# 02-USER_IO.net
KiCad netlist of a schematic drawn in Altium Designer
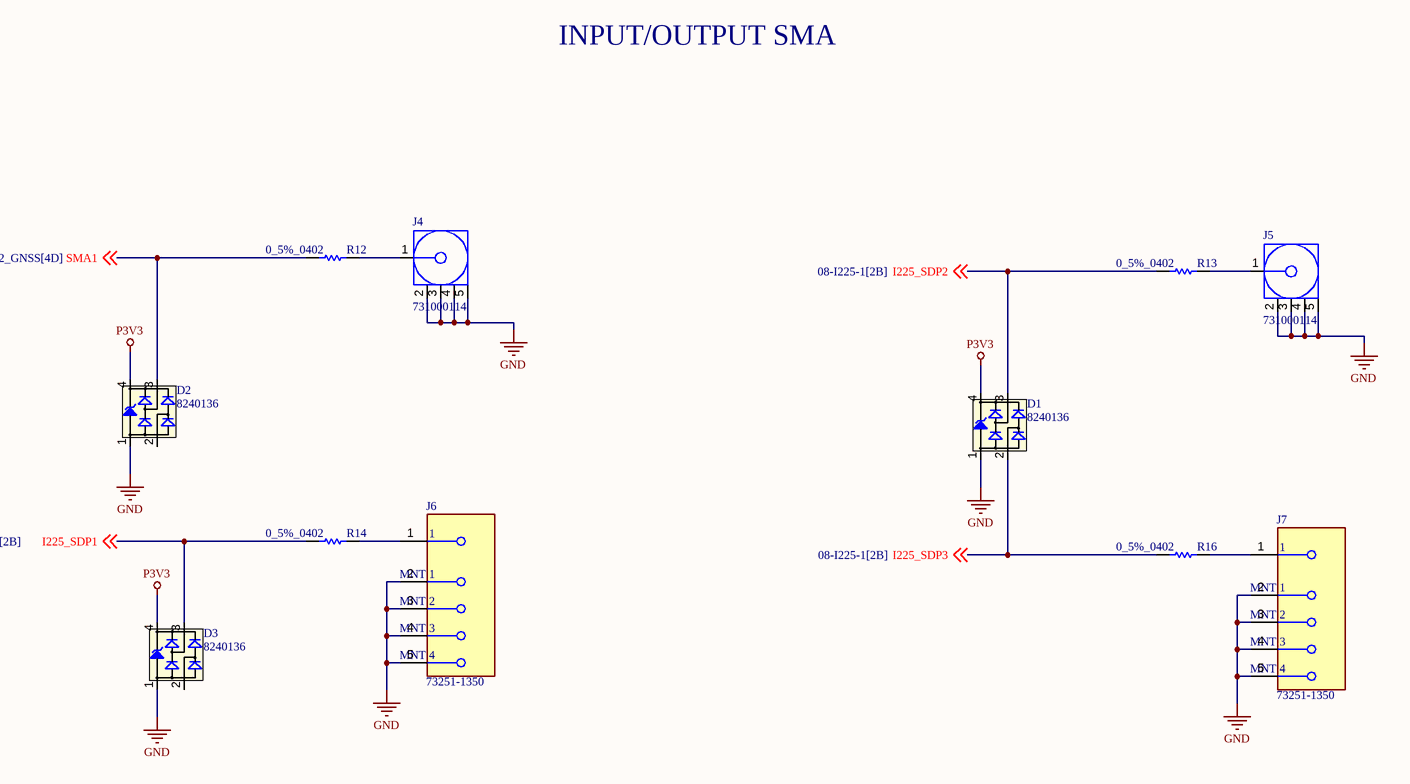
[diagram p0: 02-USER_IO.SchDoc]

(export (version "E")
  (design (tool "Eeschema 10.0.6"))
  (components
    (comp (ref "D1")
      (value "8240136")
      (footprint "SOT143-4L")
      (description "TVS Diode WE-TVS-HS, VRWM=3.3V")
      (fields (field (name "MANUFACTURER") "Wuerth Elektronik"))
      (libsource (lib "Altium Content Vault") (part "WE-TVS-HS-4"))
    )
    (comp (ref "D2")
      (value "8240136")
      (footprint "SOT143-4L")
      (description "TVS Diode WE-TVS-HS, VRWM=3.3V")
      (fields (field (name "MANUFACTURER") "Wuerth Elektronik"))
      (libsource (lib "Altium Content Vault") (part "WE-TVS-HS-4"))
    )
    (comp (ref "D3")
      (value "8240136")
      (footprint "SOT143-4L")
      (description "TVS Diode WE-TVS-HS, VRWM=3.3V")
      (fields (field (name "MANUFACTURER") "Wuerth Elektronik"))
      (libsource (lib "Altium Content Vault") (part "WE-TVS-HS-4"))
    )
    (comp (ref "J4")
      (value "731000114")
      (footprint "MOLX-731000114_V")
      (description "SMA Right-Angle PCB Jack Receptacle, Brass Body, Gold Plated, 50 Ohm, 5-Pin THD, RoHS, Tray")
      (fields (field (name "MANUFACTURER") "Molex"))
      (libsource (lib "Altium Content Vault") (part "CN-S-4F-RF5"))
    )
    (comp (ref "J5")
      (value "731000114")
      (footprint "MOLX-731000114_V")
      (description "SMA Right-Angle PCB Jack Receptacle, Brass Body, Gold Plated, 50 Ohm, 5-Pin THD, RoHS, Tray")
      (fields (field (name "MANUFACTURER") "Molex"))
      (libsource (lib "Altium Content Vault") (part "CN-S-4F-RF5"))
    )
    (comp (ref "J6")
      (value "73251-1350")
      (footprint "FP-73251-1350-MFG")
      (description "CONN SMA JACK STR 50 OHM SMD")
      (fields
        (field (name "OCTOPART") "https://octopart.com/73251-1350-molex-5414390")
        (field (name "MANUFACTURER") "Molex")
      )
      (libsource (lib "Altium Content Vault") (part "474d33b8a96b1ade9ed6dd87a2b06d4"))
    )
    (comp (ref "J7")
      (value "73251-1350")
      (footprint "FP-73251-1350-MFG")
      (description "CONN SMA JACK STR 50 OHM SMD")
      (fields
        (field (name "OCTOPART") "https://octopart.com/73251-1350-molex-5414390")
        (field (name "MANUFACTURER") "Molex")
      )
      (libsource (lib "Altium Content Vault") (part "474d33b8a96b1ade9ed6dd87a2b06d4"))
    )
    (comp (ref "R12")
      (value "0_5%_0402")
      (footprint "RESC1005X40X25LL10T10")
      (fields (field (name "MANUFACTURER") "KOA Speer") (field (name "PART NUMBER") "RK73Z1ETTP"))
      (libsource (lib "Altium Content Vault") (part "RES"))
    )
    (comp (ref "R13")
      (value "0_5%_0402")
      (footprint "RESC1005X40X25LL10T10")
      (fields (field (name "MANUFACTURER") "KOA Speer") (field (name "PART NUMBER") "RK73Z1ETTP"))
      (libsource (lib "Altium Content Vault") (part "RES"))
    )
    (comp (ref "R14")
      (value "0_5%_0402")
      (footprint "RESC1005X40X25LL10T10")
      (fields (field (name "MANUFACTURER") "KOA Speer") (field (name "PART NUMBER") "RK73Z1ETTP"))
      (libsource (lib "Altium Content Vault") (part "RES"))
    )
    (comp (ref "R16")
      (value "0_5%_0402")
      (footprint "RESC1005X40X25LL10T10")
      (fields (field (name "MANUFACTURER") "KOA Speer") (field (name "PART NUMBER") "RK73Z1ETTP"))
      (libsource (lib "Altium Content Vault") (part "RES"))
    )
  )
  (nets
    (net (code "1") (name "GND") (class "Default")
      (node (ref "D1") (pin "1") (pinfunction "GND_1") (pintype "passive"))
      (node (ref "D2") (pin "1") (pinfunction "GND_1") (pintype "passive"))
      (node (ref "D3") (pin "1") (pinfunction "GND_1") (pintype "passive"))
      (node (ref "J4") (pin "2") (pinfunction "2_2") (pintype "passive"))
      (node (ref "J4") (pin "3") (pinfunction "3_3") (pintype "passive"))
      (node (ref "J4") (pin "4") (pinfunction "4_4") (pintype "passive"))
      (node (ref "J4") (pin "5") (pinfunction "5_5") (pintype "passive"))
      (node (ref "J5") (pin "2") (pinfunction "2_2") (pintype "passive"))
      (node (ref "J5") (pin "3") (pinfunction "3_3") (pintype "passive"))
      (node (ref "J5") (pin "4") (pinfunction "4_4") (pintype "passive"))
      (node (ref "J5") (pin "5") (pinfunction "5_5") (pintype "passive"))
      (node (ref "J6") (pin "2") (pinfunction "MNT_1_2") (pintype "passive"))
      (node (ref "J6") (pin "3") (pinfunction "MNT_2_3") (pintype "passive"))
      (node (ref "J6") (pin "4") (pinfunction "MNT_3_4") (pintype "passive"))
      (node (ref "J6") (pin "5") (pinfunction "MNT_4_5") (pintype "passive"))
      (node (ref "J7") (pin "2") (pinfunction "MNT_1_2") (pintype "passive"))
      (node (ref "J7") (pin "3") (pinfunction "MNT_2_3") (pintype "passive"))
      (node (ref "J7") (pin "4") (pinfunction "MNT_3_4") (pintype "passive"))
      (node (ref "J7") (pin "5") (pinfunction "MNT_4_5") (pintype "passive"))
    )
    (net (code "2") (name "I225_SDP1") (class "Default")
      (node (ref "D3") (pin "3") (pinfunction "I/O2_3") (pintype "passive"))
      (node (ref "R14") (pin "1") (pinfunction "1_1") (pintype "passive"))
    )
    (net (code "3") (name "I225_SDP2") (class "Default")
      (node (ref "D1") (pin "3") (pinfunction "I/O2_3") (pintype "passive"))
      (node (ref "R13") (pin "1") (pinfunction "1_1") (pintype "passive"))
    )
    (net (code "4") (name "I225_SDP3") (class "Default")
      (node (ref "D1") (pin "2") (pinfunction "I/O1_2") (pintype "passive"))
      (node (ref "R16") (pin "1") (pinfunction "1_1") (pintype "passive"))
    )
    (net (code "5") (name "Net-(J4-Pad1)") (class "Default")
      (node (ref "J4") (pin "1") (pinfunction "1_1") (pintype "passive"))
      (node (ref "R12") (pin "2") (pinfunction "2_2") (pintype "passive"))
    )
    (net (code "6") (name "Net-(J5-Pad1)") (class "Default")
      (node (ref "J5") (pin "1") (pinfunction "1_1") (pintype "passive"))
      (node (ref "R13") (pin "2") (pinfunction "2_2") (pintype "passive"))
    )
    (net (code "7") (name "Net-(J6-Pad1)") (class "Default")
      (node (ref "J6") (pin "1") (pinfunction "1_1") (pintype "passive"))
      (node (ref "R14") (pin "2") (pinfunction "2_2") (pintype "passive"))
    )
    (net (code "8") (name "Net-(J7-Pad1)") (class "Default")
      (node (ref "J7") (pin "1") (pinfunction "1_1") (pintype "passive"))
      (node (ref "R16") (pin "2") (pinfunction "2_2") (pintype "passive"))
    )
    (net (code "9") (name "P3V3") (class "Default")
      (node (ref "D1") (pin "4") (pinfunction "VDD_4") (pintype "passive"))
      (node (ref "D2") (pin "4") (pinfunction "VDD_4") (pintype "passive"))
      (node (ref "D3") (pin "4") (pinfunction "VDD_4") (pintype "passive"))
    )
    (net (code "10") (name "SMA1") (class "Default")
      (node (ref "D2") (pin "3") (pinfunction "I/O2_3") (pintype "passive"))
      (node (ref "R12") (pin "1") (pinfunction "1_1") (pintype "passive"))
    )
    (net (code "11") (name "unconnected-(D2-I{slash}O1-Pad2)") (class "Default")
      (node (ref "D2") (pin "2") (pinfunction "I/O1_2") (pintype "passive"))
    )
    (net (code "12") (name "unconnected-(D3-I{slash}O1-Pad2)") (class "Default")
      (node (ref "D3") (pin "2") (pinfunction "I/O1_2") (pintype "passive"))
    )
  )
)
